# powerDistribution.net
KiCad netlist of a schematic drawn in EAGLE
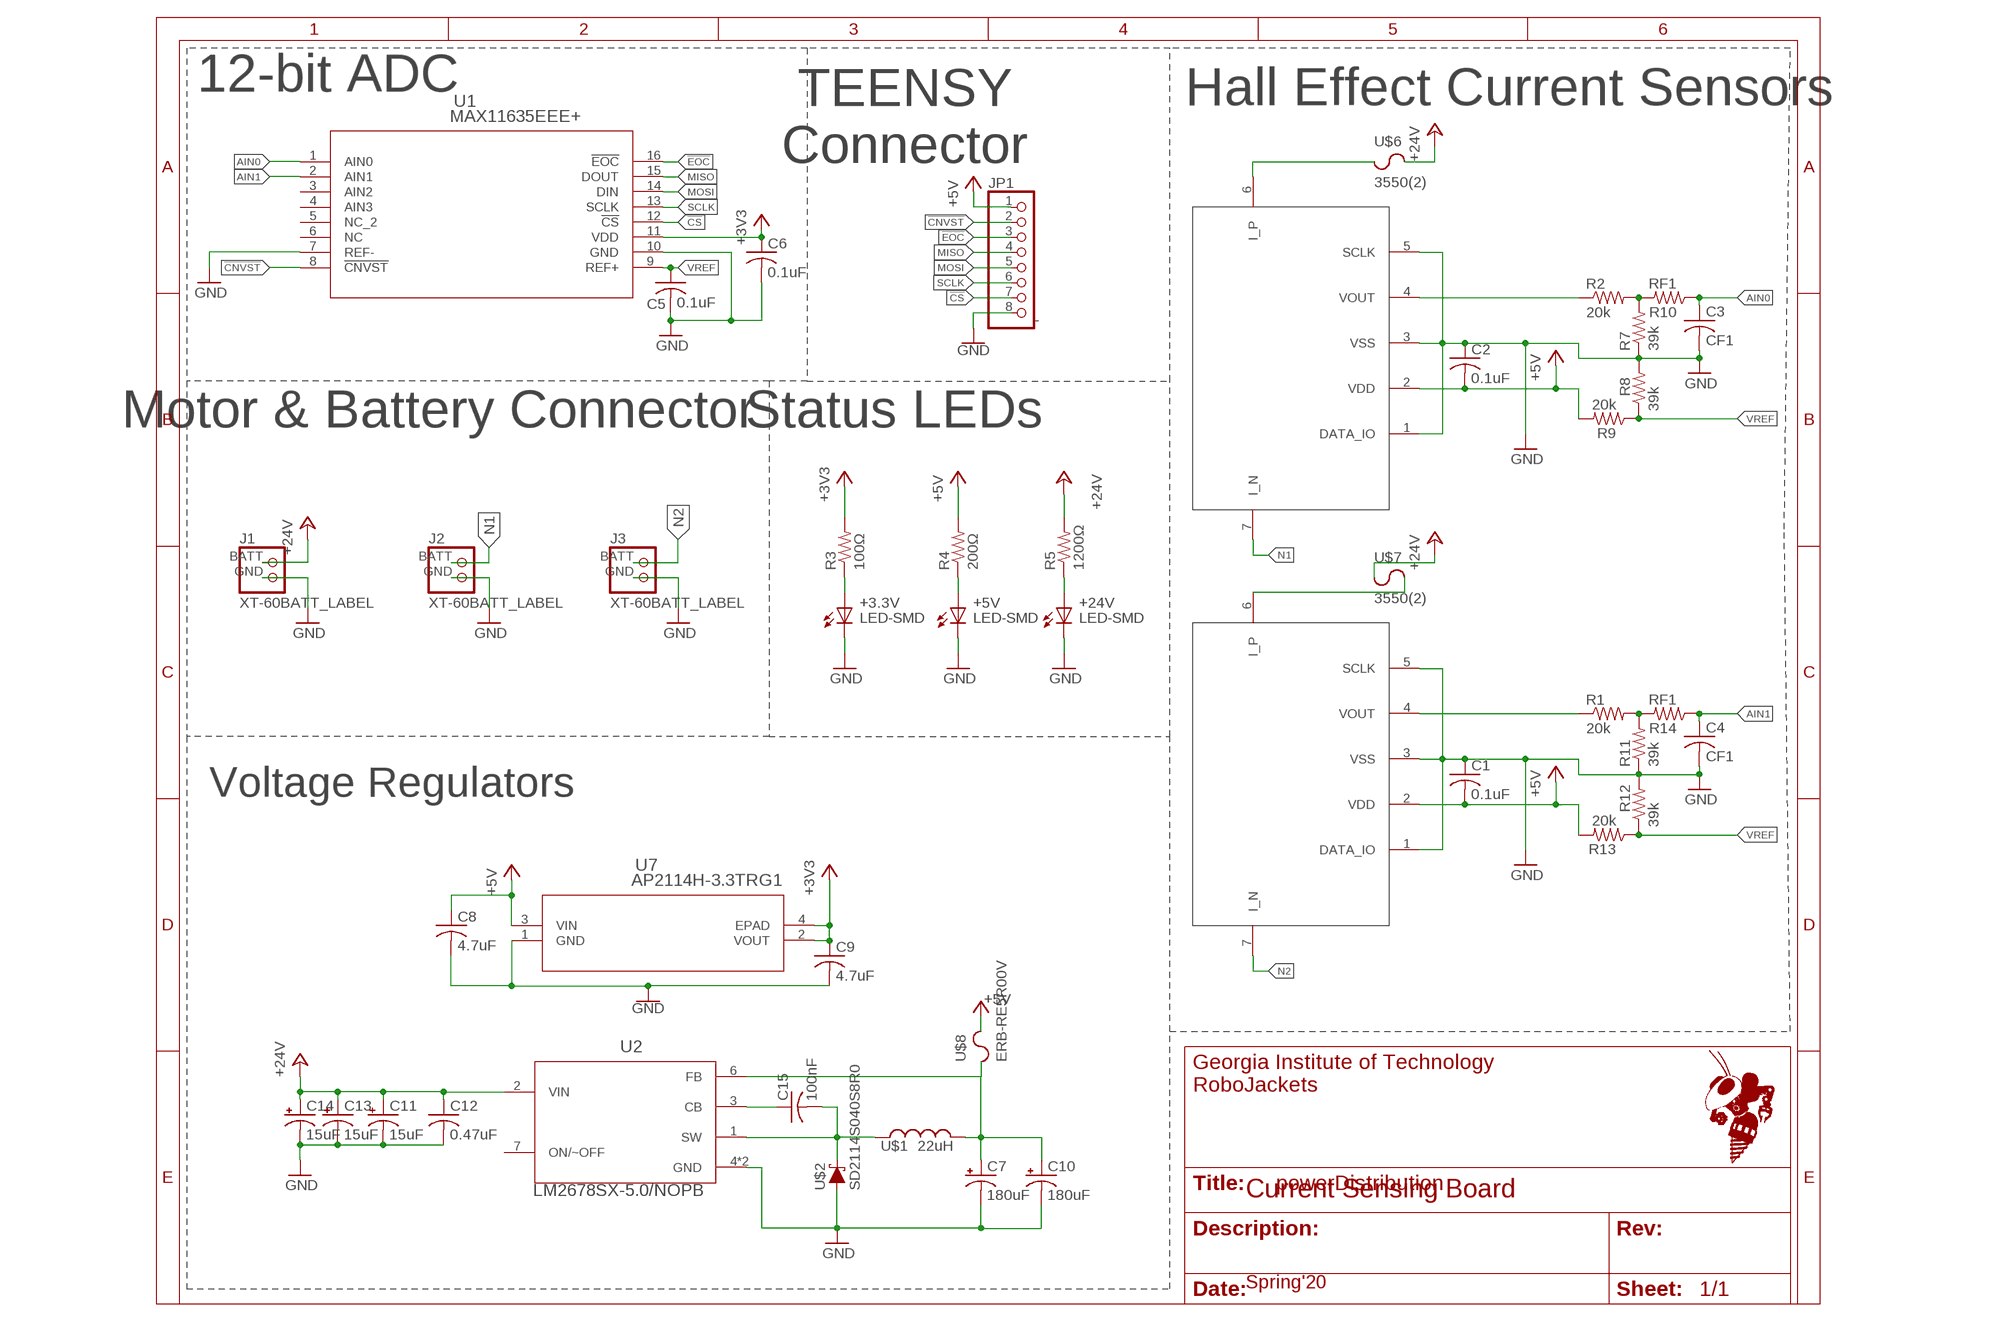
[diagram p0: schematic, sheet 1]

(export (version "E")
  (design (tool "Eeschema 10.0.6"))
  (components
    (comp (ref "+3.3V")
      (value "LED-SMD")
      (footprint "eagle-import:CHIP-LED0603")
      (libsource (lib "eagle-import") (part "LED-SMD"))
    )
    (comp (ref "+5V")
      (value "LED-SMD")
      (footprint "eagle-import:CHIP-LED0603")
      (libsource (lib "eagle-import") (part "LED-SMD"))
    )
    (comp (ref "+24V")
      (value "LED-SMD")
      (footprint "eagle-import:CHIP-LED0603")
      (libsource (lib "eagle-import") (part "LED-SMD"))
    )
    (comp (ref "C1")
      (value "0.1uF")
      (footprint "eagle-import:C0603")
      (libsource (lib "eagle-import") (part "C-USC0603"))
    )
    (comp (ref "C2")
      (value "0.1uF")
      (footprint "eagle-import:C0603")
      (libsource (lib "eagle-import") (part "C-USC0603"))
    )
    (comp (ref "C3")
      (value "CF1")
      (footprint "eagle-import:C0603")
      (libsource (lib "eagle-import") (part "C-USC0603"))
    )
    (comp (ref "C4")
      (value "CF1")
      (footprint "eagle-import:C0603")
      (libsource (lib "eagle-import") (part "C-USC0603"))
    )
    (comp (ref "C5")
      (value "0.1uF")
      (footprint "eagle-import:C0603")
      (libsource (lib "eagle-import") (part "C-USC0603"))
    )
    (comp (ref "C6")
      (value "0.1uF")
      (footprint "eagle-import:C0603")
      (libsource (lib "eagle-import") (part "C-USC0603"))
    )
    (comp (ref "C7")
      (value "180uF")
      (footprint "eagle-import:860010373009")
      (libsource (lib "eagle-import") (part "860010373009"))
    )
    (comp (ref "C8")
      (value "4.7uF")
      (footprint "eagle-import:C0603")
      (libsource (lib "eagle-import") (part "C-USC0603"))
    )
    (comp (ref "C9")
      (value "4.7uF")
      (footprint "eagle-import:C0603")
      (libsource (lib "eagle-import") (part "C-USC0603"))
    )
    (comp (ref "C10")
      (value "180uF")
      (footprint "eagle-import:860010373009")
      (libsource (lib "eagle-import") (part "860010373009"))
    )
    (comp (ref "C11")
      (value "15uF")
      (footprint "eagle-import:TR3E156M050C0300")
      (libsource (lib "eagle-import") (part "TR3E156M050C0300"))
    )
    (comp (ref "C12")
      (value "0.47uF")
      (footprint "eagle-import:C0603")
      (libsource (lib "eagle-import") (part "C-USC0603"))
    )
    (comp (ref "C13")
      (value "15uF")
      (footprint "eagle-import:TR3E156M050C0300")
      (libsource (lib "eagle-import") (part "TR3E156M050C0300"))
    )
    (comp (ref "C14")
      (value "15uF")
      (footprint "eagle-import:TR3E156M050C0300")
      (libsource (lib "eagle-import") (part "TR3E156M050C0300"))
    )
    (comp (ref "C15")
      (value "100nF")
      (footprint "eagle-import:C0603")
      (libsource (lib "eagle-import") (part "C-USC0603"))
    )
    (comp (ref "J1")
      (value "XT-60BATT_LABEL")
      (footprint "eagle-import:XT-60")
      (libsource (lib "eagle-import") (part "XT-60BATT_LABEL"))
    )
    (comp (ref "J2")
      (value "XT-60BATT_LABEL")
      (footprint "eagle-import:XT-60")
      (libsource (lib "eagle-import") (part "XT-60BATT_LABEL"))
    )
    (comp (ref "J3")
      (value "XT-60BATT_LABEL")
      (footprint "eagle-import:XT-60")
      (libsource (lib "eagle-import") (part "XT-60BATT_LABEL"))
    )
    (comp (ref "JP1")
      (value "PINHD-1X8/90")
      (footprint "eagle-import:1X08_90")
      (libsource (lib "eagle-import") (part "PINHD-1X8/90"))
    )
    (comp (ref "R1")
      (value "20k")
      (footprint "eagle-import:R0603")
      (libsource (lib "eagle-import") (part "R-US_R0603"))
    )
    (comp (ref "R2")
      (value "20k")
      (footprint "eagle-import:R0603")
      (libsource (lib "eagle-import") (part "R-US_R0603"))
    )
    (comp (ref "R3")
      (value "100Ω")
      (footprint "eagle-import:R0603")
      (libsource (lib "eagle-import") (part "R-US_R0603"))
    )
    (comp (ref "R4")
      (value "200Ω")
      (footprint "eagle-import:R0603")
      (libsource (lib "eagle-import") (part "R-US_R0603"))
    )
    (comp (ref "R5")
      (value "1200Ω")
      (footprint "eagle-import:R0603")
      (libsource (lib "eagle-import") (part "R-US_R0603"))
    )
    (comp (ref "R7")
      (value "39k")
      (footprint "eagle-import:R0603")
      (libsource (lib "eagle-import") (part "R-US_R0603"))
    )
    (comp (ref "R8")
      (value "39k")
      (footprint "eagle-import:R0603")
      (libsource (lib "eagle-import") (part "R-US_R0603"))
    )
    (comp (ref "R9")
      (value "20k")
      (footprint "eagle-import:R0603")
      (libsource (lib "eagle-import") (part "R-US_R0603"))
    )
    (comp (ref "R10")
      (value "RF1")
      (footprint "eagle-import:R0603")
      (libsource (lib "eagle-import") (part "R-US_R0603"))
    )
    (comp (ref "R11")
      (value "39k")
      (footprint "eagle-import:R0603")
      (libsource (lib "eagle-import") (part "R-US_R0603"))
    )
    (comp (ref "R12")
      (value "39k")
      (footprint "eagle-import:R0603")
      (libsource (lib "eagle-import") (part "R-US_R0603"))
    )
    (comp (ref "R13")
      (value "20k")
      (footprint "eagle-import:R0603")
      (libsource (lib "eagle-import") (part "R-US_R0603"))
    )
    (comp (ref "R14")
      (value "RF1")
      (footprint "eagle-import:R0603")
      (libsource (lib "eagle-import") (part "R-US_R0603"))
    )
    (comp (ref "U$1")
      (value "22uH")
      (footprint "eagle-import:INDUCTOR22")
      (libsource (lib "eagle-import") (part "7447709220"))
    )
    (comp (ref "U$2")
      (value "SD2114S040S8R0")
      (footprint "eagle-import:SD2114S040S8R0")
      (libsource (lib "eagle-import") (part "SD2114S040S8R0"))
    )
    (comp (ref "U$4")
      (value "CQ2065")
      (footprint "eagle-import:CQ2065")
      (libsource (lib "eagle-import") (part "CQ2065"))
    )
    (comp (ref "U$5")
      (value "CQ2065")
      (footprint "eagle-import:CQ2065")
      (libsource (lib "eagle-import") (part "CQ2065"))
    )
    (comp (ref "U$6")
      (value "3550(2)")
      (footprint "eagle-import:3550")
      (libsource (lib "eagle-import") (part "3550(2)"))
    )
    (comp (ref "U$7")
      (value "3550(2)")
      (footprint "eagle-import:3550")
      (libsource (lib "eagle-import") (part "3550(2)"))
    )
    (comp (ref "U$8")
      (value "ERB-RE5R00V")
      (footprint "eagle-import:ERB-RE5R00V")
      (libsource (lib "eagle-import") (part "ERB-RE5R00V"))
    )
    (comp (ref "U1")
      (value "MAX11635EEE+")
      (footprint "eagle-import:21-0055H_16_MXM")
      (libsource (lib "eagle-import") (part "MAX11635EEE+"))
    )
    (comp (ref "U2")
      (value "LM2678SX-5.0/NOPB")
      (footprint "eagle-import:TS7B")
      (libsource (lib "eagle-import") (part "LM2678SX-5.0/NOPB"))
    )
    (comp (ref "U7")
      (value "AP2114H-3.3TRG1")
      (footprint "eagle-import:SOT-223")
      (fields (field (name "MANUFACTURER_PART_NUMBER") "AP2114H3.3TRG1"))
      (libsource (lib "eagle-import") (part "AP2114H-3.3TRG1"))
    )
  )
  (nets
    (net (code "1") (name "+3V3") (class "Default")
      (node (ref "C6") (pin "1") (pinfunction "1_1") (pintype "passive"))
      (node (ref "C9") (pin "1") (pinfunction "1_1") (pintype "passive"))
      (node (ref "R3") (pin "2") (pinfunction "2_2") (pintype "passive"))
      (node (ref "U1") (pin "11") (pinfunction "VDD_11") (pintype "power_in"))
      (node (ref "U7") (pin "2") (pinfunction "VOUT_2") (pintype "output"))
      (node (ref "U7") (pin "4") (pinfunction "EPAD_4") (pintype "passive"))
    )
    (net (code "2") (name "+5V") (class "Default")
      (node (ref "C1") (pin "2") (pinfunction "2_2") (pintype "passive"))
      (node (ref "C2") (pin "2") (pinfunction "2_2") (pintype "passive"))
      (node (ref "C8") (pin "1") (pinfunction "1_1") (pintype "passive"))
      (node (ref "JP1") (pin "1") (pinfunction "1_1") (pintype "passive"))
      (node (ref "R13") (pin "2") (pinfunction "2_2") (pintype "passive"))
      (node (ref "R4") (pin "2") (pinfunction "2_2") (pintype "passive"))
      (node (ref "R9") (pin "2") (pinfunction "2_2") (pintype "passive"))
      (node (ref "U$4") (pin "2") (pinfunction "VDD_2") (pintype "bidirectional"))
      (node (ref "U$5") (pin "2") (pinfunction "VDD_2") (pintype "bidirectional"))
      (node (ref "U$8") (pin "P$2") (pinfunction "2_P$2") (pintype "bidirectional"))
      (node (ref "U7") (pin "3") (pinfunction "VIN_3") (pintype "input"))
    )
    (net (code "3") (name "+24V") (class "Default")
      (node (ref "C11") (pin "1") (pinfunction "+_1") (pintype "passive"))
      (node (ref "C12") (pin "1") (pinfunction "1_1") (pintype "passive"))
      (node (ref "C13") (pin "1") (pinfunction "+_1") (pintype "passive"))
      (node (ref "C14") (pin "1") (pinfunction "+_1") (pintype "passive"))
      (node (ref "J1") (pin "BATT") (pinfunction "1_BATT") (pintype "passive"))
      (node (ref "R5") (pin "2") (pinfunction "2_2") (pintype "passive"))
      (node (ref "U$6") (pin "P$2") (pinfunction "2_P$2") (pintype "bidirectional"))
      (node (ref "U$6") (pin "P$4") (pinfunction "2_P$4") (pintype "bidirectional"))
      (node (ref "U$7") (pin "P$1") (pinfunction "1_P$1") (pintype "bidirectional"))
      (node (ref "U$7") (pin "P$3") (pinfunction "1_P$3") (pintype "bidirectional"))
      (node (ref "U2") (pin "2") (pinfunction "VIN_2") (pintype "input"))
    )
    (net (code "4") (name "/~{CNVST}") (class "Default")
      (node (ref "JP1") (pin "2") (pinfunction "2_2") (pintype "passive"))
      (node (ref "U1") (pin "8") (pinfunction "~{CNVST}_8") (pintype "passive"))
    )
    (net (code "5") (name "/~{CS}") (class "Default")
      (node (ref "JP1") (pin "7") (pinfunction "7_7") (pintype "passive"))
      (node (ref "U1") (pin "12") (pinfunction "~{CS}_12") (pintype "passive"))
    )
    (net (code "6") (name "/~{EOC}") (class "Default")
      (node (ref "JP1") (pin "3") (pinfunction "3_3") (pintype "passive"))
      (node (ref "U1") (pin "16") (pinfunction "~{EOC}_16") (pintype "passive"))
    )
    (net (code "7") (name "AIN0") (class "Default")
      (node (ref "C3") (pin "1") (pinfunction "1_1") (pintype "passive"))
      (node (ref "R10") (pin "1") (pinfunction "1_1") (pintype "passive"))
      (node (ref "U1") (pin "1") (pinfunction "AIN0_1") (pintype "input"))
    )
    (net (code "8") (name "AIN1") (class "Default")
      (node (ref "C4") (pin "1") (pinfunction "1_1") (pintype "passive"))
      (node (ref "R14") (pin "1") (pinfunction "1_1") (pintype "passive"))
      (node (ref "U1") (pin "2") (pinfunction "AIN1_2") (pintype "input"))
    )
    (net (code "9") (name "GND") (class "Default")
      (node (ref "+24V") (pin "C") (pinfunction "K_C") (pintype "passive"))
      (node (ref "+3.3V") (pin "C") (pinfunction "K_C") (pintype "passive"))
      (node (ref "+5V") (pin "C") (pinfunction "K_C") (pintype "passive"))
      (node (ref "C1") (pin "1") (pinfunction "1_1") (pintype "passive"))
      (node (ref "C10") (pin "2") (pinfunction "-_2") (pintype "passive"))
      (node (ref "C11") (pin "2") (pinfunction "-_2") (pintype "passive"))
      (node (ref "C12") (pin "2") (pinfunction "2_2") (pintype "passive"))
      (node (ref "C13") (pin "2") (pinfunction "-_2") (pintype "passive"))
      (node (ref "C14") (pin "2") (pinfunction "-_2") (pintype "passive"))
      (node (ref "C2") (pin "1") (pinfunction "1_1") (pintype "passive"))
      (node (ref "C3") (pin "2") (pinfunction "2_2") (pintype "passive"))
      (node (ref "C4") (pin "2") (pinfunction "2_2") (pintype "passive"))
      (node (ref "C5") (pin "2") (pinfunction "2_2") (pintype "passive"))
      (node (ref "C6") (pin "2") (pinfunction "2_2") (pintype "passive"))
      (node (ref "C7") (pin "2") (pinfunction "-_2") (pintype "passive"))
      (node (ref "C8") (pin "2") (pinfunction "2_2") (pintype "passive"))
      (node (ref "C9") (pin "2") (pinfunction "2_2") (pintype "passive"))
      (node (ref "J1") (pin "GND") (pinfunction "2_GND") (pintype "passive"))
      (node (ref "J2") (pin "GND") (pinfunction "2_GND") (pintype "passive"))
      (node (ref "J3") (pin "GND") (pinfunction "2_GND") (pintype "passive"))
      (node (ref "JP1") (pin "8") (pinfunction "8_8") (pintype "passive"))
      (node (ref "R11") (pin "1") (pinfunction "1_1") (pintype "passive"))
      (node (ref "R12") (pin "2") (pinfunction "2_2") (pintype "passive"))
      (node (ref "R7") (pin "1") (pinfunction "1_1") (pintype "passive"))
      (node (ref "R8") (pin "2") (pinfunction "2_2") (pintype "passive"))
      (node (ref "U$2") (pin "1") (pinfunction "A_1") (pintype "passive"))
      (node (ref "U$4") (pin "1") (pinfunction "DATA_IO_1") (pintype "bidirectional"))
      (node (ref "U$4") (pin "3") (pinfunction "VSS_3") (pintype "bidirectional"))
      (node (ref "U$4") (pin "5") (pinfunction "SCLK_5") (pintype "bidirectional"))
      (node (ref "U$5") (pin "1") (pinfunction "DATA_IO_1") (pintype "bidirectional"))
      (node (ref "U$5") (pin "3") (pinfunction "VSS_3") (pintype "bidirectional"))
      (node (ref "U$5") (pin "5") (pinfunction "SCLK_5") (pintype "bidirectional"))
      (node (ref "U1") (pin "10") (pinfunction "GND_10") (pintype "power_in"))
      (node (ref "U1") (pin "7") (pinfunction "REF-_7") (pintype "passive"))
      (node (ref "U2") (pin "4") (pinfunction "GND_4") (pintype "passive"))
      (node (ref "U2") (pin "8") (pinfunction "GND_8") (pintype "passive"))
      (node (ref "U7") (pin "1") (pinfunction "GND_1") (pintype "power_in"))
    )
    (net (code "10") (name "MISO") (class "Default")
      (node (ref "JP1") (pin "4") (pinfunction "4_4") (pintype "passive"))
      (node (ref "U1") (pin "15") (pinfunction "DOUT_15") (pintype "output"))
    )
    (net (code "11") (name "MOSI") (class "Default")
      (node (ref "JP1") (pin "5") (pinfunction "5_5") (pintype "passive"))
      (node (ref "U1") (pin "14") (pinfunction "DIN_14") (pintype "input"))
    )
    (net (code "12") (name "N1") (class "Default")
      (node (ref "J2") (pin "BATT") (pinfunction "1_BATT") (pintype "passive"))
      (node (ref "U$4") (pin "7") (pinfunction "I_N_7") (pintype "bidirectional"))
    )
    (net (code "13") (name "N2") (class "Default")
      (node (ref "J3") (pin "BATT") (pinfunction "1_BATT") (pintype "passive"))
      (node (ref "U$5") (pin "7") (pinfunction "I_N_7") (pintype "bidirectional"))
    )
    (net (code "14") (name "Net-(+3.3V-PadA)") (class "Default")
      (node (ref "+3.3V") (pin "A") (pinfunction "A_A") (pintype "passive"))
      (node (ref "R3") (pin "1") (pinfunction "1_1") (pintype "passive"))
    )
    (net (code "15") (name "Net-(+5V-PadA)") (class "Default")
      (node (ref "+5V") (pin "A") (pinfunction "A_A") (pintype "passive"))
      (node (ref "R4") (pin "1") (pinfunction "1_1") (pintype "passive"))
    )
    (net (code "16") (name "Net-(+24V-PadA)") (class "Default")
      (node (ref "+24V") (pin "A") (pinfunction "A_A") (pintype "passive"))
      (node (ref "R5") (pin "1") (pinfunction "1_1") (pintype "passive"))
    )
    (net (code "17") (name "Net-(C10-+)") (class "Default")
      (node (ref "C10") (pin "1") (pinfunction "+_1") (pintype "passive"))
      (node (ref "C7") (pin "1") (pinfunction "+_1") (pintype "passive"))
      (node (ref "U$1") (pin "P$2") (pinfunction "2_P$2") (pintype "passive"))
      (node (ref "U$8") (pin "P$1") (pinfunction "1_P$1") (pintype "bidirectional"))
      (node (ref "U2") (pin "6") (pinfunction "FB_6") (pintype "passive"))
    )
    (net (code "18") (name "Net-(R1-Pad2)") (class "Default")
      (node (ref "R1") (pin "2") (pinfunction "2_2") (pintype "passive"))
      (node (ref "R11") (pin "2") (pinfunction "2_2") (pintype "passive"))
      (node (ref "R14") (pin "2") (pinfunction "2_2") (pintype "passive"))
    )
    (net (code "19") (name "Net-(R10-Pad2)") (class "Default")
      (node (ref "R10") (pin "2") (pinfunction "2_2") (pintype "passive"))
      (node (ref "R2") (pin "2") (pinfunction "2_2") (pintype "passive"))
      (node (ref "R7") (pin "2") (pinfunction "2_2") (pintype "passive"))
    )
    (net (code "20") (name "Net-(U$1-1)") (class "Default")
      (node (ref "C15") (pin "2") (pinfunction "2_2") (pintype "passive"))
      (node (ref "U$1") (pin "P$1") (pinfunction "1_P$1") (pintype "passive"))
      (node (ref "U$2") (pin "2") (pinfunction "C_2") (pintype "passive"))
      (node (ref "U2") (pin "1") (pinfunction "SW_1") (pintype "output"))
    )
    (net (code "21") (name "Net-(U$4-I_P)") (class "Default")
      (node (ref "U$4") (pin "6") (pinfunction "I_P_6") (pintype "bidirectional"))
      (node (ref "U$6") (pin "P$1") (pinfunction "1_P$1") (pintype "bidirectional"))
      (node (ref "U$6") (pin "P$3") (pinfunction "1_P$3") (pintype "bidirectional"))
    )
    (net (code "22") (name "Net-(U$4-VOUT)") (class "Default")
      (node (ref "R2") (pin "1") (pinfunction "1_1") (pintype "passive"))
      (node (ref "U$4") (pin "4") (pinfunction "VOUT_4") (pintype "bidirectional"))
    )
    (net (code "23") (name "Net-(U$5-I_P)") (class "Default")
      (node (ref "U$5") (pin "6") (pinfunction "I_P_6") (pintype "bidirectional"))
      (node (ref "U$7") (pin "P$2") (pinfunction "2_P$2") (pintype "bidirectional"))
      (node (ref "U$7") (pin "P$4") (pinfunction "2_P$4") (pintype "bidirectional"))
    )
    (net (code "24") (name "Net-(U$5-VOUT)") (class "Default")
      (node (ref "R1") (pin "1") (pinfunction "1_1") (pintype "passive"))
      (node (ref "U$5") (pin "4") (pinfunction "VOUT_4") (pintype "bidirectional"))
    )
    (net (code "25") (name "Net-(U2-CB)") (class "Default")
      (node (ref "C15") (pin "1") (pinfunction "1_1") (pintype "passive"))
      (node (ref "U2") (pin "3") (pinfunction "CB_3") (pintype "passive"))
    )
    (net (code "26") (name "SCLK") (class "Default")
      (node (ref "JP1") (pin "6") (pinfunction "6_6") (pintype "passive"))
      (node (ref "U1") (pin "13") (pinfunction "SCLK_13") (pintype "passive"))
    )
    (net (code "27") (name "VREF") (class "Default")
      (node (ref "C5") (pin "1") (pinfunction "1_1") (pintype "passive"))
      (node (ref "R12") (pin "1") (pinfunction "1_1") (pintype "passive"))
      (node (ref "R13") (pin "1") (pinfunction "1_1") (pintype "passive"))
      (node (ref "R8") (pin "1") (pinfunction "1_1") (pintype "passive"))
      (node (ref "R9") (pin "1") (pinfunction "1_1") (pintype "passive"))
      (node (ref "U1") (pin "9") (pinfunction "REF+_9") (pintype "passive"))
    )
    (net (code "28") (name "unconnected-(U1-AIN2-Pad3)") (class "Default")
      (node (ref "U1") (pin "3") (pinfunction "AIN2_3") (pintype "input"))
    )
    (net (code "29") (name "unconnected-(U1-AIN3-Pad4)") (class "Default")
      (node (ref "U1") (pin "4") (pinfunction "AIN3_4") (pintype "input"))
    )
    (net (code "30") (name "unconnected-(U1-NC-Pad6)") (class "Default")
      (node (ref "U1") (pin "6") (pinfunction "NC_6") (pintype "passive"))
    )
    (net (code "31") (name "unconnected-(U1-NC_2-Pad5)") (class "Default")
      (node (ref "U1") (pin "5") (pinfunction "NC_2_5") (pintype "passive"))
    )
    (net (code "32") (name "unconnected-(U2-ON{slash}~{OFF}-Pad7)") (class "Default")
      (node (ref "U2") (pin "7") (pinfunction "ON/~{OFF}_7") (pintype "passive"))
    )
  )
)
